# openSX70_EDWIN_V7-9-1_20191127-TSL237T.net
KiCad netlist of a schematic drawn in EAGLE
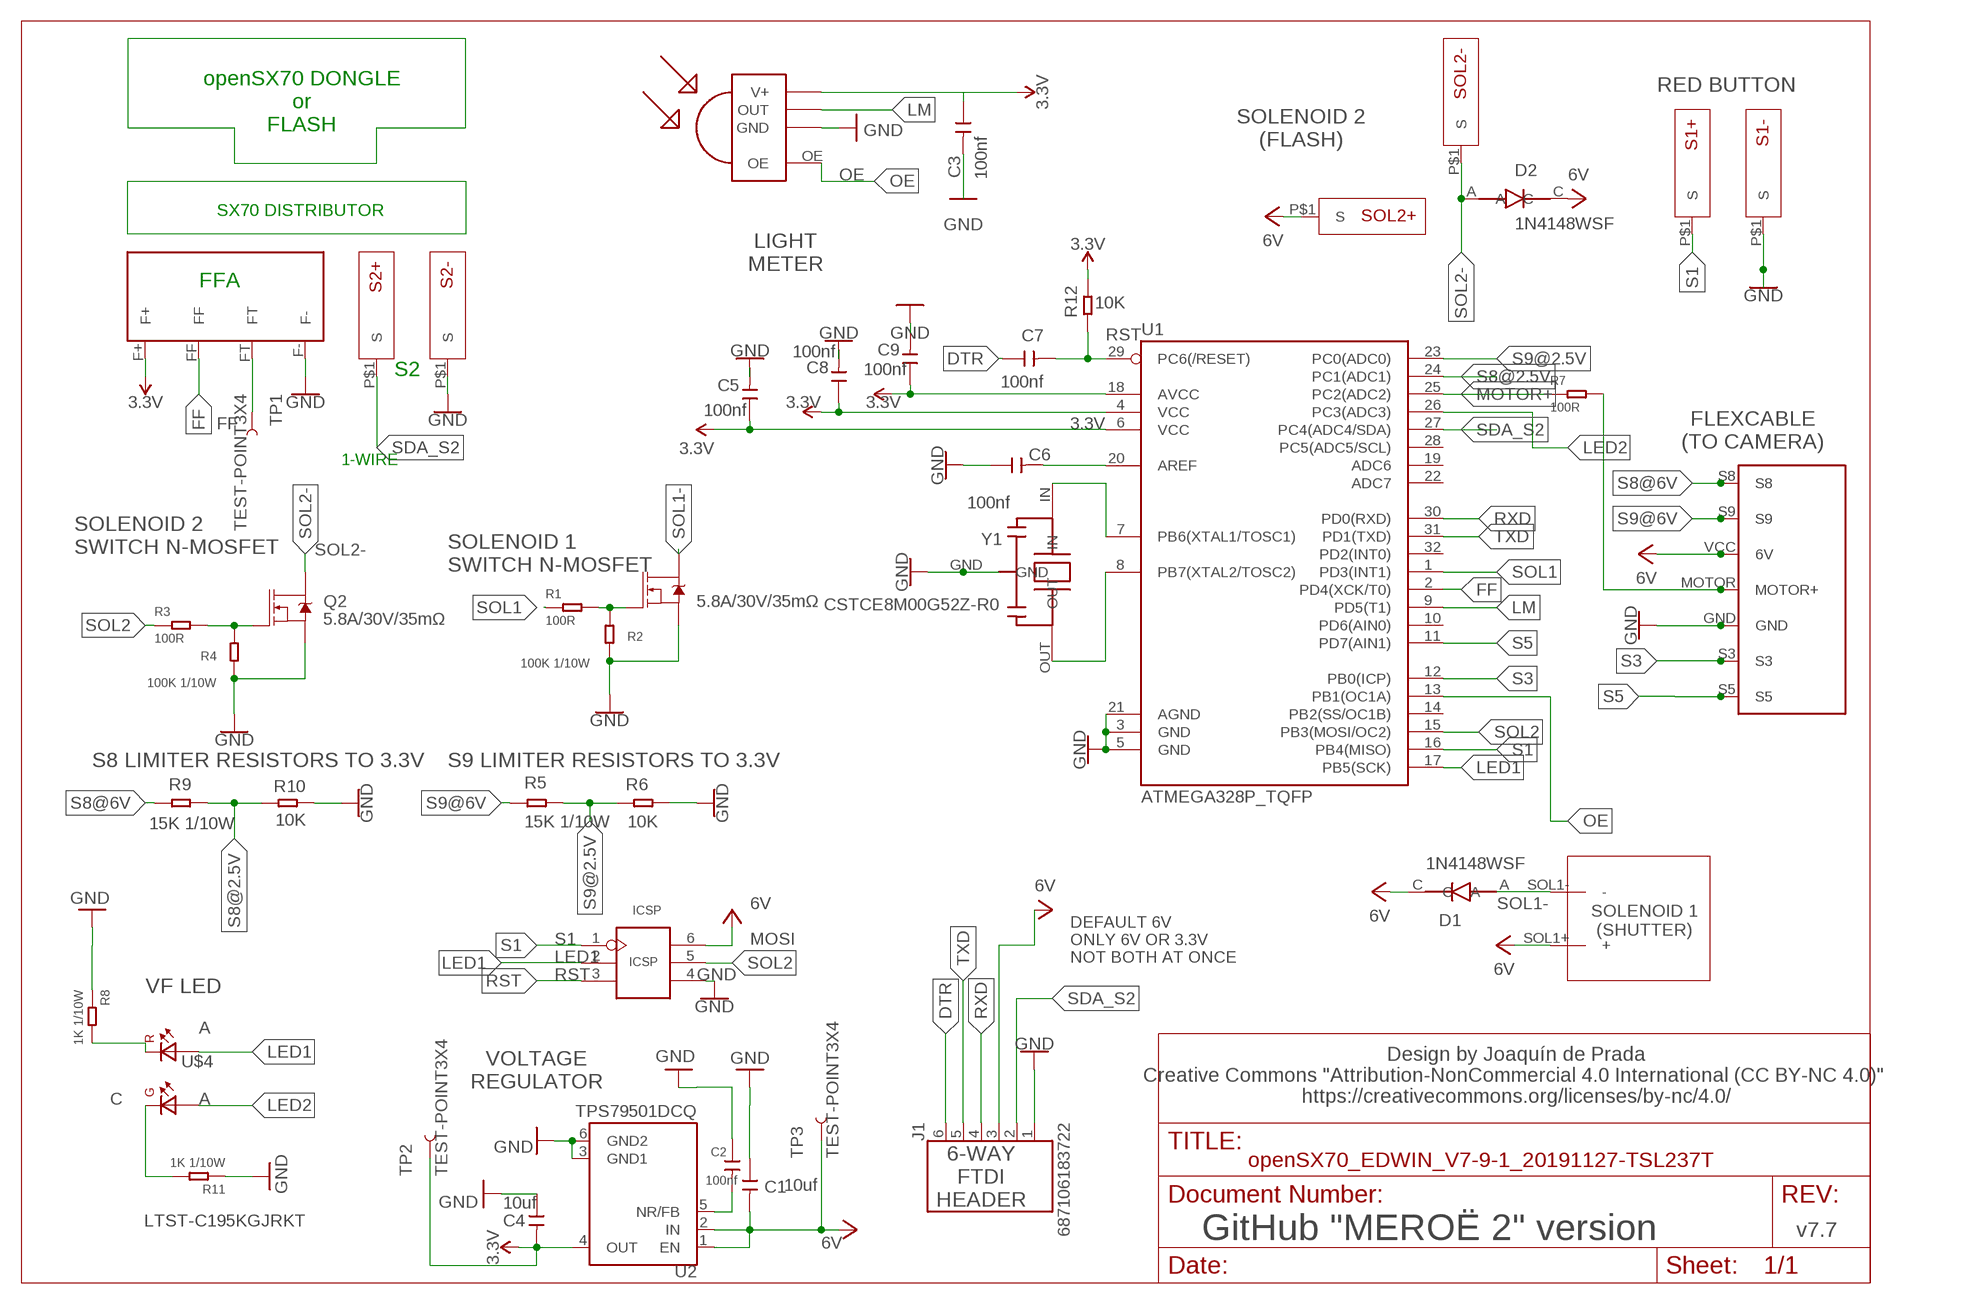
[diagram p0: schematic, sheet 1]

(export (version "E")
  (design (tool "Eeschema 10.0.6"))
  (components
    (comp (ref "C1")
      (value "10uf")
      (footprint "eagle-import:C0603")
      (fields (field (name "MPN") "CC0603KRX5R6BB106"))
      (libsource (lib "eagle-import") (part "CERAMIC-10UF-10V-10%-X5R(0603)"))
    )
    (comp (ref "C2")
      (value "100nf")
      (footprint "eagle-import:C0603")
      (fields (field (name "MPN") "CC0603KRX7R9BB104"))
      (libsource (lib "eagle-import") (part "CERAMIC-100NF-50V-10%-X7R(0603)"))
    )
    (comp (ref "C3")
      (value "100nf")
      (footprint "eagle-import:C0603")
      (fields (field (name "MPN") "CC0603KRX7R9BB104"))
      (libsource (lib "eagle-import") (part "CERAMIC-100NF-50V-10%-X7R(0603)"))
    )
    (comp (ref "C4")
      (value "10uf")
      (footprint "eagle-import:C0603")
      (fields (field (name "MPN") "CC0603KRX5R6BB106"))
      (libsource (lib "eagle-import") (part "CERAMIC-10UF-10V-10%-X5R(0603)"))
    )
    (comp (ref "C5")
      (value "100nf")
      (footprint "eagle-import:C0603")
      (fields (field (name "MPN") "CC0603KRX7R9BB104"))
      (libsource (lib "eagle-import") (part "CERAMIC-100NF-50V-10%-X7R(0603)"))
    )
    (comp (ref "C6")
      (value "100nf")
      (footprint "eagle-import:C0603")
      (fields (field (name "MPN") "CC0603KRX7R9BB104"))
      (libsource (lib "eagle-import") (part "CERAMIC-100NF-50V-10%-X7R(0603)"))
    )
    (comp (ref "C7")
      (value "100nf")
      (footprint "eagle-import:C0603")
      (fields (field (name "MPN") "CC0603KRX7R9BB104"))
      (libsource (lib "eagle-import") (part "CERAMIC-100NF-50V-10%-X7R(0603)"))
    )
    (comp (ref "C8")
      (value "100nf")
      (footprint "eagle-import:C0603")
      (fields (field (name "MPN") "CC0603KRX7R9BB104"))
      (libsource (lib "eagle-import") (part "CERAMIC-100NF-50V-10%-X7R(0603)"))
    )
    (comp (ref "C9")
      (value "100nf")
      (footprint "eagle-import:C0603")
      (fields (field (name "MPN") "CC0603KRX7R9BB104"))
      (libsource (lib "eagle-import") (part "CERAMIC-100NF-50V-10%-X7R(0603)"))
    )
    (comp (ref "D1")
      (value "1N4148WSF")
      (footprint "eagle-import:SODFL2512X100N")
      (fields (field (name "MANUFACTURER") "Fairchild Semiconductor"))
      (libsource (lib "eagle-import") (part "1N4148WS"))
    )
    (comp (ref "D2")
      (value "1N4148WSF")
      (footprint "eagle-import:SODFL2512X100N")
      (fields (field (name "MANUFACTURER") "Fairchild Semiconductor"))
      (libsource (lib "eagle-import") (part "1N4148WS"))
    )
    (comp (ref "ICSP")
      (value "ICSP")
      (footprint "eagle-import:H2X3-2.54")
      (libsource (lib "eagle-import") (part "ICSP"))
    )
    (comp (ref "J1")
      (value "687106183722")
      (footprint "eagle-import:687106183722")
      (fields (field (name "MF") "Wurth Electronics"))
      (libsource (lib "eagle-import") (part "687106183722"))
    )
    (comp (ref "Q1")
      (value "5.8A/30V/35mΩ")
      (footprint "eagle-import:SOT23-3")
      (libsource (lib "eagle-import") (part "MOSFET-NCH-AO3404A"))
    )
    (comp (ref "Q2")
      (value "5.8A/30V/35mΩ")
      (footprint "eagle-import:SOT23-3")
      (libsource (lib "eagle-import") (part "MOSFET-NCH-AO3404A"))
    )
    (comp (ref "R1")
      (value "100R")
      (footprint "eagle-import:R0603")
      (fields (field (name "MPN") "RC0603JR-07100RL"))
      (libsource (lib "eagle-import") (part "SMD-RES-100R-5%-1/10W(0603)"))
    )
    (comp (ref "R2")
      (value "100K 1/10W")
      (footprint "eagle-import:R0603")
      (fields (field (name "MPN") "RC0603JR-07100KL"))
      (libsource (lib "eagle-import") (part "SMD-RES-100K-5%-1/10W(0603)"))
    )
    (comp (ref "R3")
      (value "100R")
      (footprint "eagle-import:R0603")
      (fields (field (name "MPN") "RC0603JR-07100RL"))
      (libsource (lib "eagle-import") (part "SMD-RES-100R-5%-1/10W(0603)"))
    )
    (comp (ref "R4")
      (value "100K 1/10W")
      (footprint "eagle-import:R0603")
      (fields (field (name "MPN") "RC0603JR-07100KL"))
      (libsource (lib "eagle-import") (part "SMD-RES-100K-5%-1/10W(0603)"))
    )
    (comp (ref "R5")
      (value "15K 1/10W")
      (footprint "eagle-import:R0603")
      (fields (field (name "MPN") "RC0603FR-0715KL"))
      (libsource (lib "eagle-import") (part "SMD-RES-15K-1%-1/10W(0603)"))
    )
    (comp (ref "R6")
      (value "10K")
      (footprint "eagle-import:R0603")
      (fields (field (name "MPN") "RC0603FR-0710KL"))
      (libsource (lib "eagle-import") (part "SMD-RES-10K-1%-1/10W(0603)"))
    )
    (comp (ref "R7")
      (value "100R")
      (footprint "eagle-import:R0603")
      (fields (field (name "MPN") "RC0603JR-07100RL"))
      (libsource (lib "eagle-import") (part "SMD-RES-100R-5%-1/10W(0603)"))
    )
    (comp (ref "R8")
      (value "1K 1/10W")
      (footprint "eagle-import:R0603")
      (fields (field (name "MPN") "RC0603JR-071KL"))
      (libsource (lib "eagle-import") (part "SMD-RES-1K-5%-1/10W(0603)"))
    )
    (comp (ref "R9")
      (value "15K 1/10W")
      (footprint "eagle-import:R0603")
      (fields (field (name "MPN") "RC0603FR-0715KL"))
      (libsource (lib "eagle-import") (part "SMD-RES-15K-1%-1/10W(0603)"))
    )
    (comp (ref "R10")
      (value "10K")
      (footprint "eagle-import:R0603")
      (fields (field (name "MPN") "RC0603FR-0710KL"))
      (libsource (lib "eagle-import") (part "SMD-RES-10K-1%-1/10W(0603)"))
    )
    (comp (ref "R11")
      (value "1K 1/10W")
      (footprint "eagle-import:R0603")
      (fields (field (name "MPN") "RC0603JR-071KL"))
      (libsource (lib "eagle-import") (part "SMD-RES-1K-5%-1/10W(0603)"))
    )
    (comp (ref "R12")
      (value "10K")
      (footprint "eagle-import:R0603")
      (fields (field (name "MPN") "RC0603FR-0710KL"))
      (libsource (lib "eagle-import") (part "SMD-RES-10K-1%-1/10W(0603)"))
    )
    (comp (ref "S1+")
      (value "SX70-S-PAD-NEW")
      (footprint "eagle-import:SX70-S-PAD2")
      (libsource (lib "eagle-import") (part "SX70-S-PAD-NEW"))
    )
    (comp (ref "S1-")
      (value "SX70-S-PAD-NEW")
      (footprint "eagle-import:SX70-S-PAD2")
      (libsource (lib "eagle-import") (part "SX70-S-PAD-NEW"))
    )
    (comp (ref "S2+")
      (value "SX70-S-PAD-NEW")
      (footprint "eagle-import:SX70-S-PAD2")
      (libsource (lib "eagle-import") (part "SX70-S-PAD-NEW"))
    )
    (comp (ref "S2-")
      (value "SX70-S-PAD-NEW")
      (footprint "eagle-import:SX70-S-PAD2")
      (libsource (lib "eagle-import") (part "SX70-S-PAD-NEW"))
    )
    (comp (ref "SOL1")
      (value "SX70-SOLENOID1-2PADS")
      (footprint "eagle-import:SX70-SOLENOID1-2")
      (libsource (lib "eagle-import") (part "SX70-SOLENOID1-2PADS"))
    )
    (comp (ref "SOL2+")
      (value "SX70-S-PAD-NEW")
      (footprint "eagle-import:SX70-S-PAD2")
      (libsource (lib "eagle-import") (part "SX70-S-PAD-NEW"))
    )
    (comp (ref "SOL2-")
      (value "SX70-S-PAD-NEW")
      (footprint "eagle-import:SX70-S-PAD2")
      (libsource (lib "eagle-import") (part "SX70-S-PAD-NEW"))
    )
    (comp (ref "TP1")
      (value "TEST-POINT3X4")
      (footprint "eagle-import:PAD.03X.04")
      (libsource (lib "eagle-import") (part "TEST-POINT3X4"))
    )
    (comp (ref "TP2")
      (value "TEST-POINT3X4")
      (footprint "eagle-import:PAD.03X.04")
      (libsource (lib "eagle-import") (part "TEST-POINT3X4"))
    )
    (comp (ref "TP3")
      (value "TEST-POINT3X4")
      (footprint "eagle-import:PAD.03X.04")
      (libsource (lib "eagle-import") (part "TEST-POINT3X4"))
    )
    (comp (ref "U$1")
      (value "SX70-7-PAD")
      (footprint "eagle-import:SX70-7-PAD-PROPER")
      (libsource (lib "eagle-import") (part "SX70-7-PAD"))
    )
    (comp (ref "U$2")
      (value "FFA")
      (footprint "eagle-import:FFA-PAD-PACKAGE")
      (libsource (lib "eagle-import") (part "SX70-FFA-PAD"))
    )
    (comp (ref "U$3")
      (value "TSL237T")
      (footprint "eagle-import:TSL237T")
      (libsource (lib "eagle-import") (part "TSL237T"))
    )
    (comp (ref "U$4")
      (value "LTST-C195KGJRKT")
      (footprint "eagle-import:LTST-BILED-15X16")
      (fields (field (name "MF") "Lite-On Inc."))
      (libsource (lib "eagle-import") (part "LTST-C195KGJRKT"))
    )
    (comp (ref "U1")
      (value "ATMEGA328P_TQFP")
      (footprint "eagle-import:TQFP32-08")
      (libsource (lib "eagle-import") (part "ATMEGA328P_TQFP"))
    )
    (comp (ref "U2")
      (value "TPS79501DCQ")
      (footprint "eagle-import:SOT127P706X180-6N")
      (fields (field (name "DIGI-KEY_PART_NUMBER") "296-27102-5-ND") (field (name "MF") "Texas Instruments"))
      (libsource (lib "eagle-import") (part "TPS79501DCQ"))
    )
    (comp (ref "Y1")
      (value "CSTCE8M00G52Z-R0")
      (footprint "eagle-import:CFP95P160X100-3N")
      (fields (field (name "MF") "Murata") (field (name "MP") "CSTCE16M0V53-R0"))
      (libsource (lib "eagle-import") (part "CSTCE16M0V53-R0"))
    )
  )
  (nets
    (net (code "1") (name "3.3V") (class "Default")
      (node (ref "C3") (pin "1") (pinfunction "1_1") (pintype "passive"))
      (node (ref "C4") (pin "2") (pinfunction "2_2") (pintype "passive"))
      (node (ref "C5") (pin "1") (pinfunction "1_1") (pintype "passive"))
      (node (ref "C8") (pin "1") (pinfunction "1_1") (pintype "passive"))
      (node (ref "C9") (pin "1") (pinfunction "1_1") (pintype "passive"))
      (node (ref "R12") (pin "2") (pinfunction "2_2") (pintype "passive"))
      (node (ref "TP2") (pin "P$1") (pinfunction "1_P$1") (pintype "bidirectional"))
      (node (ref "U$2") (pin "F+") (pinfunction "F+_F+") (pintype "bidirectional"))
      (node (ref "U$3") (pin "VDD") (pinfunction "V+_VDD") (pintype "bidirectional"))
      (node (ref "U1") (pin "18") (pinfunction "AVCC_18") (pintype "bidirectional"))
      (node (ref "U1") (pin "4") (pinfunction "VCC_4") (pintype "bidirectional"))
      (node (ref "U1") (pin "6") (pinfunction "VCC_6") (pintype "bidirectional"))
      (node (ref "U2") (pin "4") (pinfunction "OUT_4") (pintype "output"))
    )
    (net (code "2") (name "6V") (class "Default")
      (node (ref "C1") (pin "2") (pinfunction "2_2") (pintype "passive"))
      (node (ref "D1") (pin "C") (pinfunction "C_C") (pintype "passive"))
      (node (ref "D2") (pin "C") (pinfunction "C_C") (pintype "passive"))
      (node (ref "ICSP") (pin "6") (pinfunction "VCC_6") (pintype "bidirectional"))
      (node (ref "J1") (pin "3") (pinfunction "4_3") (pintype "passive"))
      (node (ref "SOL1") (pin "SOL1+") (pinfunction "+_SOL1+") (pintype "bidirectional"))
      (node (ref "SOL2+") (pin "P$1") (pinfunction "S_P$1") (pintype "bidirectional"))
      (node (ref "TP3") (pin "P$1") (pinfunction "1_P$1") (pintype "bidirectional"))
      (node (ref "U$1") (pin "VCC") (pinfunction "6V_VCC") (pintype "bidirectional"))
      (node (ref "U2") (pin "1") (pinfunction "EN_1") (pintype "input"))
      (node (ref "U2") (pin "2") (pinfunction "IN_2") (pintype "input"))
    )
    (net (code "3") (name "DTR") (class "Default")
      (node (ref "C7") (pin "1") (pinfunction "1_1") (pintype "passive"))
      (node (ref "J1") (pin "6") (pinfunction "1_6") (pintype "passive"))
    )
    (net (code "4") (name "FF") (class "Default")
      (node (ref "U$2") (pin "FF") (pinfunction "FF_FF") (pintype "bidirectional"))
      (node (ref "U1") (pin "2") (pinfunction "PD4(XCK/T0)_2") (pintype "bidirectional"))
    )
    (net (code "5") (name "GND") (class "Default")
      (node (ref "C1") (pin "1") (pinfunction "1_1") (pintype "passive"))
      (node (ref "C2") (pin "1") (pinfunction "1_1") (pintype "passive"))
      (node (ref "C3") (pin "2") (pinfunction "2_2") (pintype "passive"))
      (node (ref "C4") (pin "1") (pinfunction "1_1") (pintype "passive"))
      (node (ref "C5") (pin "2") (pinfunction "2_2") (pintype "passive"))
      (node (ref "C6") (pin "1") (pinfunction "1_1") (pintype "passive"))
      (node (ref "C8") (pin "2") (pinfunction "2_2") (pintype "passive"))
      (node (ref "C9") (pin "2") (pinfunction "2_2") (pintype "passive"))
      (node (ref "ICSP") (pin "4") (pinfunction "GND_4") (pintype "bidirectional"))
      (node (ref "J1") (pin "1") (pinfunction "6_1") (pintype "passive"))
      (node (ref "Q1") (pin "2") (pinfunction "S_2") (pintype "bidirectional"))
      (node (ref "Q2") (pin "2") (pinfunction "S_2") (pintype "bidirectional"))
      (node (ref "R10") (pin "2") (pinfunction "2_2") (pintype "passive"))
      (node (ref "R11") (pin "1") (pinfunction "1_1") (pintype "passive"))
      (node (ref "R2") (pin "1") (pinfunction "1_1") (pintype "passive"))
      (node (ref "R4") (pin "1") (pinfunction "1_1") (pintype "passive"))
      (node (ref "R6") (pin "2") (pinfunction "2_2") (pintype "passive"))
      (node (ref "R8") (pin "1") (pinfunction "1_1") (pintype "passive"))
      (node (ref "S1-") (pin "P$1") (pinfunction "S_P$1") (pintype "bidirectional"))
      (node (ref "S2-") (pin "P$1") (pinfunction "S_P$1") (pintype "bidirectional"))
      (node (ref "U$1") (pin "GND") (pinfunction "GND_GND") (pintype "bidirectional"))
      (node (ref "U$2") (pin "F-") (pinfunction "F-_F-") (pintype "bidirectional"))
      (node (ref "U$3") (pin "GND") (pinfunction "GND_GND") (pintype "bidirectional"))
      (node (ref "U1") (pin "21") (pinfunction "AGND_21") (pintype "bidirectional"))
      (node (ref "U1") (pin "3") (pinfunction "GND_3") (pintype "bidirectional"))
      (node (ref "U1") (pin "5") (pinfunction "GND_5") (pintype "bidirectional"))
      (node (ref "U2") (pin "3") (pinfunction "GND1_3") (pintype "power_in"))
      (node (ref "U2") (pin "6") (pinfunction "GND2_6") (pintype "power_in"))
      (node (ref "Y1") (pin "GND") (pinfunction "GND_GND") (pintype "passive"))
    )
    (net (code "6") (name "LED1") (class "Default")
      (node (ref "ICSP") (pin "2") (pinfunction "SCK_2") (pintype "bidirectional"))
      (node (ref "U$4") (pin "P$2") (pinfunction "A2_P$2") (pintype "passive"))
      (node (ref "U1") (pin "17") (pinfunction "PB5(SCK)_17") (pintype "bidirectional"))
    )
    (net (code "7") (name "LED2") (class "Default")
      (node (ref "U$4") (pin "P$1") (pinfunction "A1_P$1") (pintype "passive"))
      (node (ref "U1") (pin "26") (pinfunction "PC3(ADC3)_26") (pintype "bidirectional"))
    )
    (net (code "8") (name "LM") (class "Default")
      (node (ref "U$3") (pin "OUT") (pinfunction "OUT_OUT") (pintype "bidirectional"))
      (node (ref "U1") (pin "9") (pinfunction "PD5(T1)_9") (pintype "bidirectional"))
    )
    (net (code "9") (name "MOTOR+") (class "Default")
      (node (ref "R7") (pin "1") (pinfunction "1_1") (pintype "passive"))
      (node (ref "U1") (pin "25") (pinfunction "PC2(ADC2)_25") (pintype "bidirectional"))
    )
    (net (code "10") (name "Net-(Q1-G)") (class "Default")
      (node (ref "Q1") (pin "1") (pinfunction "G_1") (pintype "bidirectional"))
      (node (ref "R1") (pin "2") (pinfunction "2_2") (pintype "passive"))
      (node (ref "R2") (pin "2") (pinfunction "2_2") (pintype "passive"))
    )
    (net (code "11") (name "Net-(Q2-G)") (class "Default")
      (node (ref "Q2") (pin "1") (pinfunction "G_1") (pintype "bidirectional"))
      (node (ref "R3") (pin "2") (pinfunction "2_2") (pintype "passive"))
      (node (ref "R4") (pin "2") (pinfunction "2_2") (pintype "passive"))
    )
    (net (code "12") (name "Net-(TP1-1)") (class "Default")
      (node (ref "TP1") (pin "P$1") (pinfunction "1_P$1") (pintype "bidirectional"))
      (node (ref "U$2") (pin "FT") (pinfunction "FT_FT") (pintype "bidirectional"))
    )
    (net (code "13") (name "Net-(U$1-MOTOR+)") (class "Default")
      (node (ref "R7") (pin "2") (pinfunction "2_2") (pintype "passive"))
      (node (ref "U$1") (pin "MOTOR") (pinfunction "MOTOR+_MOTOR") (pintype "bidirectional"))
    )
    (net (code "14") (name "Net-(U$4-K1)") (class "Default")
      (node (ref "R11") (pin "2") (pinfunction "2_2") (pintype "passive"))
      (node (ref "U$4") (pin "P$3") (pinfunction "K1_P$3") (pintype "passive"))
    )
    (net (code "15") (name "Net-(U$4-K2)") (class "Default")
      (node (ref "R8") (pin "2") (pinfunction "2_2") (pintype "passive"))
      (node (ref "U$4") (pin "P$4") (pinfunction "K2_P$4") (pintype "passive"))
    )
    (net (code "16") (name "Net-(U1-AREF)") (class "Default")
      (node (ref "C6") (pin "2") (pinfunction "2_2") (pintype "passive"))
      (node (ref "U1") (pin "20") (pinfunction "AREF_20") (pintype "bidirectional"))
    )
    (net (code "17") (name "Net-(U1-PB6(XTAL1{slash}TOSC1))") (class "Default")
      (node (ref "U1") (pin "7") (pinfunction "PB6(XTAL1/TOSC1)_7") (pintype "bidirectional"))
      (node (ref "Y1") (pin "IN") (pinfunction "IN_IN") (pintype "input"))
    )
    (net (code "18") (name "Net-(U1-PB7(XTAL2{slash}TOSC2))") (class "Default")
      (node (ref "U1") (pin "8") (pinfunction "PB7(XTAL2/TOSC2)_8") (pintype "bidirectional"))
      (node (ref "Y1") (pin "OUT") (pinfunction "OUT_OUT") (pintype "output"))
    )
    (net (code "19") (name "Net-(U2-NR{slash}FB)") (class "Default")
      (node (ref "C2") (pin "2") (pinfunction "2_2") (pintype "passive"))
      (node (ref "U2") (pin "5") (pinfunction "NR/FB_5") (pintype "input"))
    )
    (net (code "20") (name "OE") (class "Default")
      (node (ref "U$3") (pin "OE") (pinfunction "OE_OE") (pintype "bidirectional"))
      (node (ref "U1") (pin "13") (pinfunction "PB1(OC1A)_13") (pintype "bidirectional"))
    )
    (net (code "21") (name "RST") (class "Default")
      (node (ref "C7") (pin "2") (pinfunction "2_2") (pintype "passive"))
      (node (ref "ICSP") (pin "3") (pinfunction "RST_3") (pintype "bidirectional"))
      (node (ref "R12") (pin "1") (pinfunction "1_1") (pintype "passive"))
      (node (ref "U1") (pin "29") (pinfunction "PC6(/RESET)_29") (pintype "bidirectional"))
    )
    (net (code "22") (name "RXD") (class "Default")
      (node (ref "J1") (pin "4") (pinfunction "3_4") (pintype "passive"))
      (node (ref "U1") (pin "30") (pinfunction "PD0(RXD)_30") (pintype "bidirectional"))
    )
    (net (code "23") (name "S1") (class "Default")
      (node (ref "ICSP") (pin "1") (pinfunction "MISO_1") (pintype "bidirectional"))
      (node (ref "S1+") (pin "P$1") (pinfunction "S_P$1") (pintype "bidirectional"))
      (node (ref "U1") (pin "16") (pinfunction "PB4(MISO)_16") (pintype "bidirectional"))
    )
    (net (code "24") (name "S3") (class "Default")
      (node (ref "U$1") (pin "S3") (pinfunction "S3_S3") (pintype "bidirectional"))
      (node (ref "U1") (pin "12") (pinfunction "PB0(ICP)_12") (pintype "bidirectional"))
    )
    (net (code "25") (name "S5") (class "Default")
      (node (ref "U$1") (pin "S5") (pinfunction "S5_S5") (pintype "bidirectional"))
      (node (ref "U1") (pin "11") (pinfunction "PD7(AIN1)_11") (pintype "bidirectional"))
    )
    (net (code "26") (name "S8@2.5V") (class "Default")
      (node (ref "R10") (pin "1") (pinfunction "1_1") (pintype "passive"))
      (node (ref "R9") (pin "2") (pinfunction "2_2") (pintype "passive"))
      (node (ref "U1") (pin "24") (pinfunction "PC1(ADC1)_24") (pintype "bidirectional"))
    )
    (net (code "27") (name "S8@6V") (class "Default")
      (node (ref "R9") (pin "1") (pinfunction "1_1") (pintype "passive"))
      (node (ref "U$1") (pin "S8") (pinfunction "S8_S8") (pintype "bidirectional"))
    )
    (net (code "28") (name "S9@2.5V") (class "Default")
      (node (ref "R5") (pin "2") (pinfunction "2_2") (pintype "passive"))
      (node (ref "R6") (pin "1") (pinfunction "1_1") (pintype "passive"))
      (node (ref "U1") (pin "23") (pinfunction "PC0(ADC0)_23") (pintype "bidirectional"))
    )
    (net (code "29") (name "S9@6V") (class "Default")
      (node (ref "R5") (pin "1") (pinfunction "1_1") (pintype "passive"))
      (node (ref "U$1") (pin "S9") (pinfunction "S9_S9") (pintype "bidirectional"))
    )
    (net (code "30") (name "SDA_S2") (class "Default")
      (node (ref "J1") (pin "2") (pinfunction "5_2") (pintype "passive"))
      (node (ref "S2+") (pin "P$1") (pinfunction "S_P$1") (pintype "bidirectional"))
      (node (ref "U1") (pin "27") (pinfunction "PC4(ADC4/SDA)_27") (pintype "bidirectional"))
    )
    (net (code "31") (name "SOL1") (class "Default")
      (node (ref "R1") (pin "1") (pinfunction "1_1") (pintype "passive"))
      (node (ref "U1") (pin "1") (pinfunction "PD3(INT1)_1") (pintype "bidirectional"))
    )
    (net (code "32") (name "SOL1-") (class "Default")
      (node (ref "D1") (pin "A") (pinfunction "A_A") (pintype "passive"))
      (node (ref "Q1") (pin "3") (pinfunction "D_3") (pintype "bidirectional"))
      (node (ref "SOL1") (pin "SOL1-") (pinfunction "-_SOL1-") (pintype "bidirectional"))
    )
    (net (code "33") (name "SOL2") (class "Default")
      (node (ref "ICSP") (pin "5") (pinfunction "MOSI_5") (pintype "bidirectional"))
      (node (ref "R3") (pin "1") (pinfunction "1_1") (pintype "passive"))
      (node (ref "U1") (pin "15") (pinfunction "PB3(MOSI/OC2)_15") (pintype "bidirectional"))
    )
    (net (code "34") (name "SOL2-") (class "Default")
      (node (ref "D2") (pin "A") (pinfunction "A_A") (pintype "passive"))
      (node (ref "Q2") (pin "3") (pinfunction "D_3") (pintype "bidirectional"))
      (node (ref "SOL2-") (pin "P$1") (pinfunction "S_P$1") (pintype "bidirectional"))
    )
    (net (code "35") (name "TXD") (class "Default")
      (node (ref "J1") (pin "5") (pinfunction "2_5") (pintype "passive"))
      (node (ref "U1") (pin "31") (pinfunction "PD1(TXD)_31") (pintype "bidirectional"))
    )
    (net (code "36") (name "unconnected-(U1-ADC6-Pad19)") (class "Default")
      (node (ref "U1") (pin "19") (pinfunction "ADC6_19") (pintype "bidirectional"))
    )
    (net (code "37") (name "unconnected-(U1-ADC7-Pad22)") (class "Default")
      (node (ref "U1") (pin "22") (pinfunction "ADC7_22") (pintype "bidirectional"))
    )
    (net (code "38") (name "unconnected-(U1-PB2(SS{slash}OC1B)-Pad14)") (class "Default")
      (node (ref "U1") (pin "14") (pinfunction "PB2(SS/OC1B)_14") (pintype "bidirectional"))
    )
    (net (code "39") (name "unconnected-(U1-PC5(ADC5{slash}SCL)-Pad28)") (class "Default")
      (node (ref "U1") (pin "28") (pinfunction "PC5(ADC5/SCL)_28") (pintype "bidirectional"))
    )
    (net (code "40") (name "unconnected-(U1-PD2(INT0)-Pad32)") (class "Default")
      (node (ref "U1") (pin "32") (pinfunction "PD2(INT0)_32") (pintype "bidirectional"))
    )
    (net (code "41") (name "unconnected-(U1-PD6(AIN0)-Pad10)") (class "Default")
      (node (ref "U1") (pin "10") (pinfunction "PD6(AIN0)_10") (pintype "bidirectional"))
    )
  )
)
